# Wifi_Module.net
KiCad netlist of a schematic drawn in Altium Designer
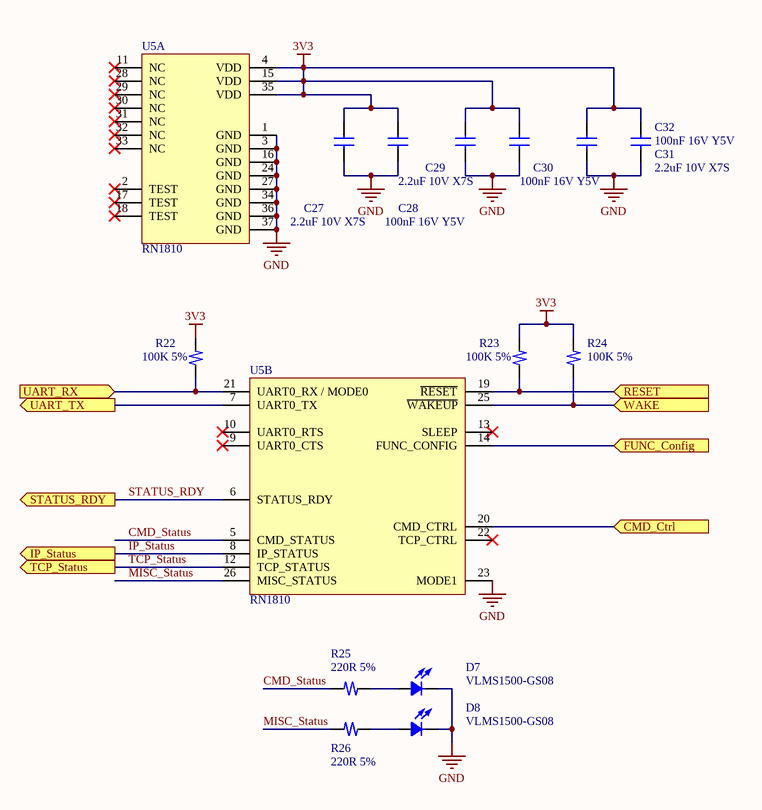
[diagram p0: Wifi_Module.SchDoc]

(export (version "E")
  (design (tool "Eeschema 10.0.6"))
  (components
    (comp (ref "C27")
      (value "2.2uF 10V X7S")
      (footprint "C_0402")
      (description "Ceramic Capacitor SMD 0402")
      (libsource (lib "Oxy_Lib") (part "Ceramic Capacitor"))
    )
    (comp (ref "C28")
      (value "100nF 16V Y5V")
      (footprint "C_0402")
      (description "Ceramic Capacitor SMD 0402")
      (libsource (lib "Oxy_Lib") (part "Ceramic Capacitor"))
    )
    (comp (ref "C29")
      (value "2.2uF 10V X7S")
      (footprint "C_0402")
      (description "Ceramic Capacitor SMD 0402")
      (libsource (lib "Oxy_Lib") (part "Ceramic Capacitor"))
    )
    (comp (ref "C30")
      (value "100nF 16V Y5V")
      (footprint "C_0402")
      (description "Ceramic Capacitor SMD 0402")
      (libsource (lib "Oxy_Lib") (part "Ceramic Capacitor"))
    )
    (comp (ref "C31")
      (value "2.2uF 10V X7S")
      (footprint "C_0402")
      (description "Ceramic Capacitor SMD 0402")
      (libsource (lib "Oxy_Lib") (part "Ceramic Capacitor"))
    )
    (comp (ref "C32")
      (value "100nF 16V Y5V")
      (footprint "C_0402")
      (description "Ceramic Capacitor SMD 0402")
      (libsource (lib "Oxy_Lib") (part "Ceramic Capacitor"))
    )
    (comp (ref "D7")
      (value "VLMS1500-GS08")
      (footprint "L_0402")
      (description "LED Diode SMD 0402")
      (libsource (lib "Oxy_Lib") (part "Diode LED"))
    )
    (comp (ref "D8")
      (value "VLMS1500-GS08")
      (footprint "L_0402")
      (description "LED Diode SMD 0402")
      (libsource (lib "Oxy_Lib") (part "Diode LED"))
    )
    (comp (ref "R22")
      (value "100K 5%")
      (footprint "R_0402")
      (description "Resistor SMD 0402")
      (libsource (lib "Oxy_Lib") (part "Resistor"))
    )
    (comp (ref "R23")
      (value "100K 5%")
      (footprint "R_0402")
      (description "Resistor SMD 0402")
      (libsource (lib "Oxy_Lib") (part "Resistor"))
    )
    (comp (ref "R24")
      (value "100K 5%")
      (footprint "R_0402")
      (description "Resistor SMD 0402")
      (libsource (lib "Oxy_Lib") (part "Resistor"))
    )
    (comp (ref "R25")
      (value "220R 5%")
      (footprint "R_0402")
      (description "Resistor SMD 0402")
      (libsource (lib "Oxy_Lib") (part "Resistor"))
    )
    (comp (ref "R26")
      (value "220R 5%")
      (footprint "R_0402")
      (description "Resistor SMD 0402")
      (libsource (lib "Oxy_Lib") (part "Resistor"))
    )
    (comp (ref "U5")
      (value "RN1810")
      (footprint "RN1810")
      (description "2.4 GHz IEEE 802.11b/g/n Wireless Module RN1810")
      (libsource (lib "Oxy_Lib") (part "RN1810 Wifi Module"))
    )
  )
  (nets
    (net (code "1") (name "/CMD_Ctrl") (class "Default")
      (node (ref "U5") (pin "20") (pinfunction "CMD_CTRL_20") (pintype "passive"))
    )
    (net (code "2") (name "/CMD_Status") (class "Default")
      (node (ref "R25") (pin "1") (pinfunction "1_1") (pintype "passive"))
      (node (ref "U5") (pin "5") (pinfunction "CMD_STATUS_5") (pintype "passive"))
    )
    (net (code "3") (name "/FUNC_Config") (class "Default")
      (node (ref "U5") (pin "14") (pinfunction "FUNC_CONFIG_14") (pintype "passive"))
    )
    (net (code "4") (name "/IP_Status") (class "Default")
      (node (ref "U5") (pin "8") (pinfunction "IP_STATUS_8") (pintype "passive"))
    )
    (net (code "5") (name "/MISC_Status") (class "Default")
      (node (ref "R26") (pin "1") (pinfunction "1_1") (pintype "passive"))
      (node (ref "U5") (pin "26") (pinfunction "MISC_STATUS_26") (pintype "passive"))
    )
    (net (code "6") (name "/RESET") (class "Default")
      (node (ref "R23") (pin "1") (pinfunction "1_1") (pintype "passive"))
      (node (ref "U5") (pin "19") (pinfunction "~{RESET}_19") (pintype "passive"))
    )
    (net (code "7") (name "/STATUS_RDY") (class "Default")
      (node (ref "U5") (pin "6") (pinfunction "STATUS_RDY_6") (pintype "passive"))
    )
    (net (code "8") (name "/TCP_Status") (class "Default")
      (node (ref "U5") (pin "12") (pinfunction "TCP_STATUS_12") (pintype "passive"))
    )
    (net (code "9") (name "/UART_RX") (class "Default")
      (node (ref "R22") (pin "1") (pinfunction "1_1") (pintype "passive"))
      (node (ref "U5") (pin "21") (pinfunction "UART0_RX_/_MODE0_21") (pintype "passive"))
    )
    (net (code "10") (name "/UART_TX") (class "Default")
      (node (ref "U5") (pin "7") (pinfunction "UART0_TX_7") (pintype "passive"))
    )
    (net (code "11") (name "/WAKE") (class "Default")
      (node (ref "R24") (pin "1") (pinfunction "1_1") (pintype "passive"))
      (node (ref "U5") (pin "25") (pinfunction "~{WAKEUP}_25") (pintype "passive"))
    )
    (net (code "12") (name "3V3") (class "Default")
      (node (ref "C27") (pin "1") (pinfunction "1_1") (pintype "passive"))
      (node (ref "C28") (pin "1") (pinfunction "1_1") (pintype "passive"))
      (node (ref "C29") (pin "1") (pinfunction "1_1") (pintype "passive"))
      (node (ref "C30") (pin "1") (pinfunction "1_1") (pintype "passive"))
      (node (ref "C31") (pin "1") (pinfunction "1_1") (pintype "passive"))
      (node (ref "C32") (pin "1") (pinfunction "1_1") (pintype "passive"))
      (node (ref "R22") (pin "2") (pinfunction "2_2") (pintype "passive"))
      (node (ref "R23") (pin "2") (pinfunction "2_2") (pintype "passive"))
      (node (ref "R24") (pin "2") (pinfunction "2_2") (pintype "passive"))
      (node (ref "U5") (pin "15") (pinfunction "VDD_15") (pintype "passive"))
      (node (ref "U5") (pin "35") (pinfunction "VDD_35") (pintype "passive"))
      (node (ref "U5") (pin "4") (pinfunction "VDD_4") (pintype "passive"))
    )
    (net (code "13") (name "GND") (class "Default")
      (node (ref "C27") (pin "2") (pinfunction "2_2") (pintype "passive"))
      (node (ref "C28") (pin "2") (pinfunction "2_2") (pintype "passive"))
      (node (ref "C29") (pin "2") (pinfunction "2_2") (pintype "passive"))
      (node (ref "C30") (pin "2") (pinfunction "2_2") (pintype "passive"))
      (node (ref "C31") (pin "2") (pinfunction "2_2") (pintype "passive"))
      (node (ref "C32") (pin "2") (pinfunction "2_2") (pintype "passive"))
      (node (ref "D7") (pin "2") (pinfunction "2_2") (pintype "passive"))
      (node (ref "D8") (pin "2") (pinfunction "2_2") (pintype "passive"))
      (node (ref "U5") (pin "1") (pinfunction "GND_1") (pintype "passive"))
      (node (ref "U5") (pin "16") (pinfunction "GND_16") (pintype "passive"))
      (node (ref "U5") (pin "23") (pinfunction "MODE1_23") (pintype "passive"))
      (node (ref "U5") (pin "24") (pinfunction "GND_24") (pintype "passive"))
      (node (ref "U5") (pin "27") (pinfunction "GND_27") (pintype "passive"))
      (node (ref "U5") (pin "3") (pinfunction "GND_3") (pintype "passive"))
      (node (ref "U5") (pin "34") (pinfunction "GND_34") (pintype "passive"))
      (node (ref "U5") (pin "36") (pinfunction "GND_36") (pintype "passive"))
      (node (ref "U5") (pin "37") (pinfunction "GND_37") (pintype "passive"))
    )
    (net (code "14") (name "Net-(D7-Pad1)") (class "Default")
      (node (ref "D7") (pin "1") (pinfunction "1_1") (pintype "passive"))
      (node (ref "R25") (pin "2") (pinfunction "2_2") (pintype "passive"))
    )
    (net (code "15") (name "Net-(D8-Pad1)") (class "Default")
      (node (ref "D8") (pin "1") (pinfunction "1_1") (pintype "passive"))
      (node (ref "R26") (pin "2") (pinfunction "2_2") (pintype "passive"))
    )
    (net (code "16") (name "unconnected-(U5A-NC-Pad11)") (class "Default")
      (node (ref "U5") (pin "11") (pinfunction "NC_11") (pintype "passive+no_connect"))
    )
    (net (code "17") (name "unconnected-(U5A-NC-Pad28)") (class "Default")
      (node (ref "U5") (pin "28") (pinfunction "NC_28") (pintype "passive+no_connect"))
    )
    (net (code "18") (name "unconnected-(U5A-NC-Pad29)") (class "Default")
      (node (ref "U5") (pin "29") (pinfunction "NC_29") (pintype "passive+no_connect"))
    )
    (net (code "19") (name "unconnected-(U5A-NC-Pad30)") (class "Default")
      (node (ref "U5") (pin "30") (pinfunction "NC_30") (pintype "passive+no_connect"))
    )
    (net (code "20") (name "unconnected-(U5A-NC-Pad31)") (class "Default")
      (node (ref "U5") (pin "31") (pinfunction "NC_31") (pintype "passive+no_connect"))
    )
    (net (code "21") (name "unconnected-(U5A-NC-Pad32)") (class "Default")
      (node (ref "U5") (pin "32") (pinfunction "NC_32") (pintype "passive+no_connect"))
    )
    (net (code "22") (name "unconnected-(U5A-NC-Pad33)") (class "Default")
      (node (ref "U5") (pin "33") (pinfunction "NC_33") (pintype "passive+no_connect"))
    )
    (net (code "23") (name "unconnected-(U5A-TEST-Pad2)") (class "Default")
      (node (ref "U5") (pin "2") (pinfunction "TEST_2") (pintype "passive+no_connect"))
    )
    (net (code "24") (name "unconnected-(U5A-TEST-Pad17)") (class "Default")
      (node (ref "U5") (pin "17") (pinfunction "TEST_17") (pintype "passive+no_connect"))
    )
    (net (code "25") (name "unconnected-(U5A-TEST-Pad18)") (class "Default")
      (node (ref "U5") (pin "18") (pinfunction "TEST_18") (pintype "passive+no_connect"))
    )
    (net (code "26") (name "unconnected-(U5B-SLEEP-Pad13)") (class "Default")
      (node (ref "U5") (pin "13") (pinfunction "SLEEP_13") (pintype "passive+no_connect"))
    )
    (net (code "27") (name "unconnected-(U5B-TCP_CTRL-Pad22)") (class "Default")
      (node (ref "U5") (pin "22") (pinfunction "TCP_CTRL_22") (pintype "passive+no_connect"))
    )
    (net (code "28") (name "unconnected-(U5B-UART0_CTS-Pad9)") (class "Default")
      (node (ref "U5") (pin "9") (pinfunction "UART0_CTS_9") (pintype "passive+no_connect"))
    )
    (net (code "29") (name "unconnected-(U5B-UART0_RTS-Pad10)") (class "Default")
      (node (ref "U5") (pin "10") (pinfunction "UART0_RTS_10") (pintype "passive+no_connect"))
    )
  )
)
